# 03_Mos.net
KiCad netlist of a schematic drawn in Altium Designer
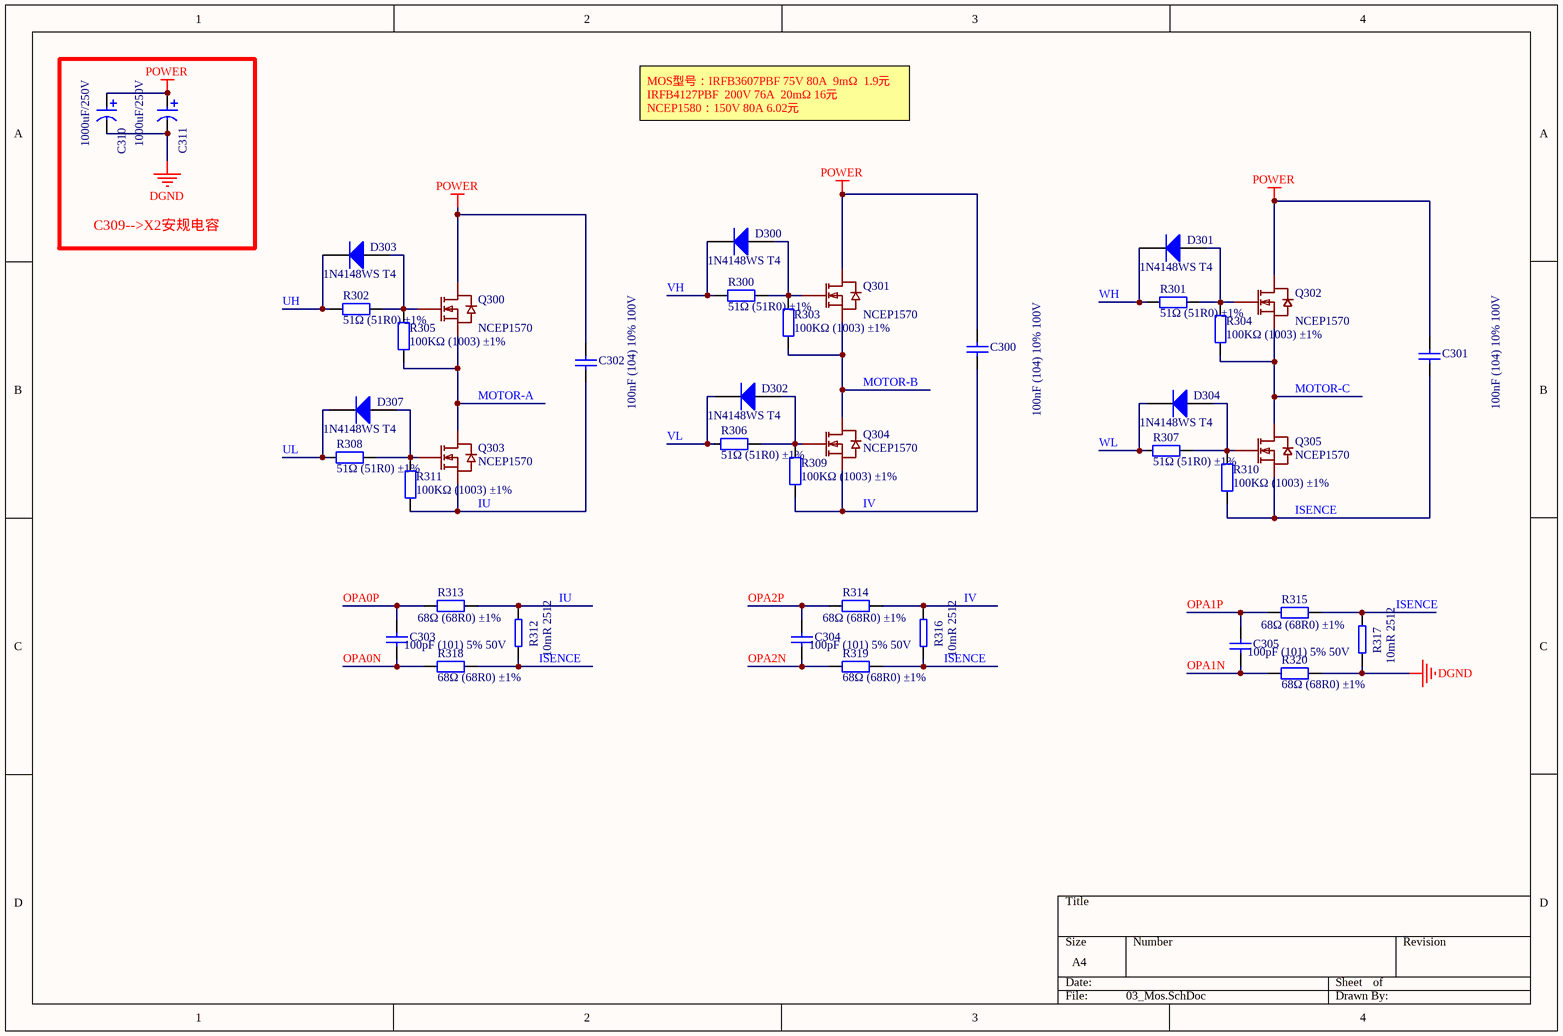
[diagram p0: 03_Mos.SchDoc]

(export (version "E")
  (design (tool "Eeschema 10.0.6"))
  (components
    (comp (ref "C300")
      (value "100nF (104) 10% 100V")
      (footprint "1206_C")
      (description "贴片电容")
      (libsource (lib "Miscellaneous Devices LC") (part "1206 100nF (104) 10% 50V"))
    )
    (comp (ref "C301")
      (value "100nF (104) 10% 100V")
      (footprint "1206_C")
      (description "贴片电容")
      (libsource (lib "Miscellaneous Devices LC") (part "1206 100nF (104) 10% 50V"))
    )
    (comp (ref "C302")
      (value "100nF (104) 10% 100V")
      (footprint "1206_C")
      (description "贴片电容")
      (libsource (lib "Miscellaneous Devices LC") (part "1206 100nF (104) 10% 50V"))
    )
    (comp (ref "C303")
      (value "100pF (101) 5% 50V")
      (footprint "0805_C")
      (description "贴片电容")
      (libsource (lib "Miscellaneous Devices LC") (part "0805 100pF (101) 5% 50V"))
    )
    (comp (ref "C304")
      (value "100pF (101) 5% 50V")
      (footprint "0805_C")
      (description "贴片电容")
      (libsource (lib "Miscellaneous Devices LC") (part "0805 100pF (101) 5% 50V"))
    )
    (comp (ref "C305")
      (value "100pF (101) 5% 50V")
      (footprint "0805_C")
      (description "贴片电容")
      (libsource (lib "Miscellaneous Devices LC") (part "0805 100pF (101) 5% 50V"))
    )
    (comp (ref "C310")
      (value "1000uF/250V")
      (footprint "1000uf/250V")
      (description "电解电容")
      (libsource (lib "Schlibv2") (part "CAP2"))
    )
    (comp (ref "C311")
      (value "1000uF/250V")
      (footprint "1000uf/250V")
      (description "电解电容")
      (libsource (lib "Schlibv2") (part "CAP2"))
    )
    (comp (ref "D300")
      (value "1N4148WS T4")
      (footprint "SOD-323")
      (description "二极管")
      (libsource (lib "Miscellaneous Devices LC") (part "SOD-323 1N4148WS T4"))
    )
    (comp (ref "D301")
      (value "1N4148WS T4")
      (footprint "SOD-323")
      (description "二极管")
      (libsource (lib "Miscellaneous Devices LC") (part "SOD-323 1N4148WS T4"))
    )
    (comp (ref "D302")
      (value "1N4148WS T4")
      (footprint "SOD-323")
      (description "二极管")
      (libsource (lib "Miscellaneous Devices LC") (part "SOD-323 1N4148WS T4"))
    )
    (comp (ref "D303")
      (value "1N4148WS T4")
      (footprint "SOD-323")
      (description "二极管")
      (libsource (lib "Miscellaneous Devices LC") (part "SOD-323 1N4148WS T4"))
    )
    (comp (ref "D304")
      (value "1N4148WS T4")
      (footprint "SOD-323")
      (description "二极管")
      (libsource (lib "Miscellaneous Devices LC") (part "SOD-323 1N4148WS T4"))
    )
    (comp (ref "D307")
      (value "1N4148WS T4")
      (footprint "SOD-323")
      (description "二极管")
      (libsource (lib "Miscellaneous Devices LC") (part "SOD-323 1N4148WS T4"))
    )
    (comp (ref "Q300")
      (value "NCEP1570")
      (footprint "NCEP1570")
      (libsource (lib "RayPCB20210502") (part "IRFB4127PBF"))
    )
    (comp (ref "Q301")
      (value "NCEP1570")
      (footprint "NCEP1570")
      (libsource (lib "RayPCB20210502") (part "IRFB4127PBF"))
    )
    (comp (ref "Q302")
      (value "NCEP1570")
      (footprint "NCEP1570")
      (libsource (lib "RayPCB20210502") (part "IRFB4127PBF"))
    )
    (comp (ref "Q303")
      (value "NCEP1570")
      (footprint "NCEP1570")
      (libsource (lib "RayPCB20210502") (part "IRFB4127PBF"))
    )
    (comp (ref "Q304")
      (value "NCEP1570")
      (footprint "NCEP1570")
      (libsource (lib "RayPCB20210502") (part "IRFB4127PBF"))
    )
    (comp (ref "Q305")
      (value "NCEP1570")
      (footprint "NCEP1570")
      (libsource (lib "RayPCB20210502") (part "IRFB4127PBF"))
    )
    (comp (ref "R300")
      (value "51Ω (51R0) ±1%")
      (footprint "0805_R")
      (description "贴片电阻")
      (libsource (lib "Miscellaneous Devices LC") (part "0805 51Ω (51R0) 1%"))
    )
    (comp (ref "R301")
      (value "51Ω (51R0) ±1%")
      (footprint "0805_R")
      (description "贴片电阻")
      (libsource (lib "Miscellaneous Devices LC") (part "0805 51Ω (51R0) 1%"))
    )
    (comp (ref "R302")
      (value "51Ω (51R0) ±1%")
      (footprint "0805_R")
      (description "贴片电阻")
      (libsource (lib "Miscellaneous Devices LC") (part "0805 51Ω (51R0) 1%"))
    )
    (comp (ref "R303")
      (value "100KΩ (1003) ±1%")
      (footprint "0805_R")
      (description "贴片电阻")
      (libsource (lib "Miscellaneous Devices LC") (part "0805 100KΩ (1003) 1%"))
    )
    (comp (ref "R304")
      (value "100KΩ (1003) ±1%")
      (footprint "0805_R")
      (description "贴片电阻")
      (libsource (lib "Miscellaneous Devices LC") (part "0805 100KΩ (1003) 1%"))
    )
    (comp (ref "R305")
      (value "100KΩ (1003) ±1%")
      (footprint "0805_R")
      (description "贴片电阻")
      (libsource (lib "Miscellaneous Devices LC") (part "0805 100KΩ (1003) 1%"))
    )
    (comp (ref "R306")
      (value "51Ω (51R0) ±1%")
      (footprint "0805_R")
      (description "贴片电阻")
      (libsource (lib "Miscellaneous Devices LC") (part "0805 51Ω (51R0) 1%"))
    )
    (comp (ref "R307")
      (value "51Ω (51R0) ±1%")
      (footprint "0805_R")
      (description "贴片电阻")
      (libsource (lib "Miscellaneous Devices LC") (part "0805 51Ω (51R0) 1%"))
    )
    (comp (ref "R308")
      (value "51Ω (51R0) ±1%")
      (footprint "0805_R")
      (description "贴片电阻")
      (libsource (lib "Miscellaneous Devices LC") (part "0805 51Ω (51R0) 1%"))
    )
    (comp (ref "R309")
      (value "100KΩ (1003) ±1%")
      (footprint "0805_R")
      (description "贴片电阻")
      (libsource (lib "Miscellaneous Devices LC") (part "0805 100KΩ (1003) 1%"))
    )
    (comp (ref "R310")
      (value "100KΩ (1003) ±1%")
      (footprint "0805_R")
      (description "贴片电阻")
      (libsource (lib "Miscellaneous Devices LC") (part "0805 100KΩ (1003) 1%"))
    )
    (comp (ref "R311")
      (value "100KΩ (1003) ±1%")
      (footprint "0805_R")
      (description "贴片电阻")
      (libsource (lib "Miscellaneous Devices LC") (part "0805 100KΩ (1003) 1%"))
    )
    (comp (ref "R312")
      (value "10mR 2512")
      (footprint "R2512")
      (libsource (lib "RayPCB20210502") (part "Res10K"))
    )
    (comp (ref "R313")
      (value "68Ω (68R0) ±1%")
      (footprint "0805_R")
      (description "贴片电阻")
      (libsource (lib "Miscellaneous Devices LC") (part "0805 68Ω (68R0) 1%"))
    )
    (comp (ref "R314")
      (value "68Ω (68R0) ±1%")
      (footprint "0805_R")
      (description "贴片电阻")
      (libsource (lib "Miscellaneous Devices LC") (part "0805 68Ω (68R0) 1%"))
    )
    (comp (ref "R315")
      (value "68Ω (68R0) ±1%")
      (footprint "0805_R")
      (description "贴片电阻")
      (libsource (lib "Miscellaneous Devices LC") (part "0805 68Ω (68R0) 1%"))
    )
    (comp (ref "R316")
      (value "10mR 2512")
      (footprint "R2512")
      (libsource (lib "RayPCB20210502") (part "Res10K"))
    )
    (comp (ref "R317")
      (value "10mR 2512")
      (footprint "R2512")
      (libsource (lib "RayPCB20210502") (part "Res10K"))
    )
    (comp (ref "R318")
      (value "68Ω (68R0) ±1%")
      (footprint "0805_R")
      (description "贴片电阻")
      (libsource (lib "Miscellaneous Devices LC") (part "0805 68Ω (68R0) 1%"))
    )
    (comp (ref "R319")
      (value "68Ω (68R0) ±1%")
      (footprint "0805_R")
      (description "贴片电阻")
      (libsource (lib "Miscellaneous Devices LC") (part "0805 68Ω (68R0) 1%"))
    )
    (comp (ref "R320")
      (value "68Ω (68R0) ±1%")
      (footprint "0805_R")
      (description "贴片电阻")
      (libsource (lib "Miscellaneous Devices LC") (part "0805 68Ω (68R0) 1%"))
    )
  )
  (nets
    (net (code "1") (name "/ISENCE") (class "Default")
      (node (ref "C301") (pin "1") (pinfunction "1_1") (pintype "passive"))
      (node (ref "Q305") (pin "3") (pinfunction "S_3") (pintype "passive"))
      (node (ref "R310") (pin "1") (pinfunction "1_1") (pintype "passive"))
      (node (ref "R312") (pin "1") (pintype "passive"))
      (node (ref "R315") (pin "2") (pinfunction "2_2") (pintype "passive"))
      (node (ref "R316") (pin "1") (pintype "passive"))
      (node (ref "R317") (pin "2") (pintype "passive"))
      (node (ref "R318") (pin "2") (pinfunction "2_2") (pintype "passive"))
      (node (ref "R319") (pin "2") (pinfunction "2_2") (pintype "passive"))
    )
    (net (code "2") (name "/IU") (class "Default")
      (node (ref "C302") (pin "1") (pinfunction "1_1") (pintype "passive"))
      (node (ref "Q303") (pin "3") (pinfunction "S_3") (pintype "passive"))
      (node (ref "R311") (pin "1") (pinfunction "1_1") (pintype "passive"))
      (node (ref "R312") (pin "2") (pintype "passive"))
      (node (ref "R313") (pin "2") (pinfunction "2_2") (pintype "passive"))
    )
    (net (code "3") (name "/IV") (class "Default")
      (node (ref "C300") (pin "1") (pinfunction "1_1") (pintype "passive"))
      (node (ref "Q304") (pin "3") (pinfunction "S_3") (pintype "passive"))
      (node (ref "R309") (pin "1") (pinfunction "1_1") (pintype "passive"))
      (node (ref "R314") (pin "2") (pinfunction "2_2") (pintype "passive"))
      (node (ref "R316") (pin "2") (pintype "passive"))
    )
    (net (code "4") (name "/MOTOR-A") (class "Default")
      (node (ref "Q300") (pin "3") (pinfunction "S_3") (pintype "passive"))
      (node (ref "Q303") (pin "2") (pinfunction "D_2") (pintype "passive"))
      (node (ref "R305") (pin "1") (pinfunction "1_1") (pintype "passive"))
    )
    (net (code "5") (name "/MOTOR-B") (class "Default")
      (node (ref "Q301") (pin "3") (pinfunction "S_3") (pintype "passive"))
      (node (ref "Q304") (pin "2") (pinfunction "D_2") (pintype "passive"))
      (node (ref "R303") (pin "1") (pinfunction "1_1") (pintype "passive"))
    )
    (net (code "6") (name "/MOTOR-C") (class "Default")
      (node (ref "Q302") (pin "3") (pinfunction "S_3") (pintype "passive"))
      (node (ref "Q305") (pin "2") (pinfunction "D_2") (pintype "passive"))
      (node (ref "R304") (pin "1") (pinfunction "1_1") (pintype "passive"))
    )
    (net (code "7") (name "/OPA0N") (class "Default")
      (node (ref "C303") (pin "1") (pinfunction "1_1") (pintype "passive"))
      (node (ref "R318") (pin "1") (pinfunction "1_1") (pintype "passive"))
    )
    (net (code "8") (name "/OPA0P") (class "Default")
      (node (ref "C303") (pin "2") (pinfunction "2_2") (pintype "passive"))
      (node (ref "R313") (pin "1") (pinfunction "1_1") (pintype "passive"))
    )
    (net (code "9") (name "/OPA1N") (class "Default")
      (node (ref "C305") (pin "1") (pinfunction "1_1") (pintype "passive"))
      (node (ref "R320") (pin "1") (pinfunction "1_1") (pintype "passive"))
    )
    (net (code "10") (name "/OPA1P") (class "Default")
      (node (ref "C305") (pin "2") (pinfunction "2_2") (pintype "passive"))
      (node (ref "R315") (pin "1") (pinfunction "1_1") (pintype "passive"))
    )
    (net (code "11") (name "/OPA2N") (class "Default")
      (node (ref "C304") (pin "1") (pinfunction "1_1") (pintype "passive"))
      (node (ref "R319") (pin "1") (pinfunction "1_1") (pintype "passive"))
    )
    (net (code "12") (name "/OPA2P") (class "Default")
      (node (ref "C304") (pin "2") (pinfunction "2_2") (pintype "passive"))
      (node (ref "R314") (pin "1") (pinfunction "1_1") (pintype "passive"))
    )
    (net (code "13") (name "/UH") (class "Default")
      (node (ref "D303") (pin "2") (pinfunction "K_2") (pintype "passive"))
      (node (ref "R302") (pin "1") (pinfunction "1_1") (pintype "passive"))
    )
    (net (code "14") (name "/UL") (class "Default")
      (node (ref "D307") (pin "2") (pinfunction "K_2") (pintype "passive"))
      (node (ref "R308") (pin "1") (pinfunction "1_1") (pintype "passive"))
    )
    (net (code "15") (name "/VH") (class "Default")
      (node (ref "D300") (pin "2") (pinfunction "K_2") (pintype "passive"))
      (node (ref "R300") (pin "1") (pinfunction "1_1") (pintype "passive"))
    )
    (net (code "16") (name "/VL") (class "Default")
      (node (ref "D302") (pin "2") (pinfunction "K_2") (pintype "passive"))
      (node (ref "R306") (pin "1") (pinfunction "1_1") (pintype "passive"))
    )
    (net (code "17") (name "/WH") (class "Default")
      (node (ref "D301") (pin "2") (pinfunction "K_2") (pintype "passive"))
      (node (ref "R301") (pin "1") (pinfunction "1_1") (pintype "passive"))
    )
    (net (code "18") (name "/WL") (class "Default")
      (node (ref "D304") (pin "2") (pinfunction "K_2") (pintype "passive"))
      (node (ref "R307") (pin "1") (pinfunction "1_1") (pintype "passive"))
    )
    (net (code "19") (name "DGND") (class "Default")
      (node (ref "C310") (pin "2") (pintype "passive"))
      (node (ref "C311") (pin "2") (pintype "passive"))
      (node (ref "R317") (pin "1") (pintype "passive"))
      (node (ref "R320") (pin "2") (pinfunction "2_2") (pintype "passive"))
    )
    (net (code "20") (name "Net-(D300-A)") (class "Default")
      (node (ref "D300") (pin "1") (pinfunction "A_1") (pintype "passive"))
      (node (ref "Q301") (pin "1") (pinfunction "G_1") (pintype "passive"))
      (node (ref "R300") (pin "2") (pinfunction "2_2") (pintype "passive"))
      (node (ref "R303") (pin "2") (pinfunction "2_2") (pintype "passive"))
    )
    (net (code "21") (name "Net-(D301-A)") (class "Default")
      (node (ref "D301") (pin "1") (pinfunction "A_1") (pintype "passive"))
      (node (ref "Q302") (pin "1") (pinfunction "G_1") (pintype "passive"))
      (node (ref "R301") (pin "2") (pinfunction "2_2") (pintype "passive"))
      (node (ref "R304") (pin "2") (pinfunction "2_2") (pintype "passive"))
    )
    (net (code "22") (name "Net-(D302-A)") (class "Default")
      (node (ref "D302") (pin "1") (pinfunction "A_1") (pintype "passive"))
      (node (ref "Q304") (pin "1") (pinfunction "G_1") (pintype "passive"))
      (node (ref "R306") (pin "2") (pinfunction "2_2") (pintype "passive"))
      (node (ref "R309") (pin "2") (pinfunction "2_2") (pintype "passive"))
    )
    (net (code "23") (name "Net-(D303-A)") (class "Default")
      (node (ref "D303") (pin "1") (pinfunction "A_1") (pintype "passive"))
      (node (ref "Q300") (pin "1") (pinfunction "G_1") (pintype "passive"))
      (node (ref "R302") (pin "2") (pinfunction "2_2") (pintype "passive"))
      (node (ref "R305") (pin "2") (pinfunction "2_2") (pintype "passive"))
    )
    (net (code "24") (name "Net-(D304-A)") (class "Default")
      (node (ref "D304") (pin "1") (pinfunction "A_1") (pintype "passive"))
      (node (ref "Q305") (pin "1") (pinfunction "G_1") (pintype "passive"))
      (node (ref "R307") (pin "2") (pinfunction "2_2") (pintype "passive"))
      (node (ref "R310") (pin "2") (pinfunction "2_2") (pintype "passive"))
    )
    (net (code "25") (name "Net-(D307-A)") (class "Default")
      (node (ref "D307") (pin "1") (pinfunction "A_1") (pintype "passive"))
      (node (ref "Q303") (pin "1") (pinfunction "G_1") (pintype "passive"))
      (node (ref "R308") (pin "2") (pinfunction "2_2") (pintype "passive"))
      (node (ref "R311") (pin "2") (pinfunction "2_2") (pintype "passive"))
    )
    (net (code "26") (name "POWER") (class "Default")
      (node (ref "C300") (pin "2") (pinfunction "2_2") (pintype "passive"))
      (node (ref "C301") (pin "2") (pinfunction "2_2") (pintype "passive"))
      (node (ref "C302") (pin "2") (pinfunction "2_2") (pintype "passive"))
      (node (ref "C310") (pin "1") (pintype "passive"))
      (node (ref "C311") (pin "1") (pintype "passive"))
      (node (ref "Q300") (pin "2") (pinfunction "D_2") (pintype "passive"))
      (node (ref "Q301") (pin "2") (pinfunction "D_2") (pintype "passive"))
      (node (ref "Q302") (pin "2") (pinfunction "D_2") (pintype "passive"))
    )
  )
)
